# SAM_E54_Xplained_Pro_current_measurement.net
KiCad netlist of a schematic drawn in Altium Designer
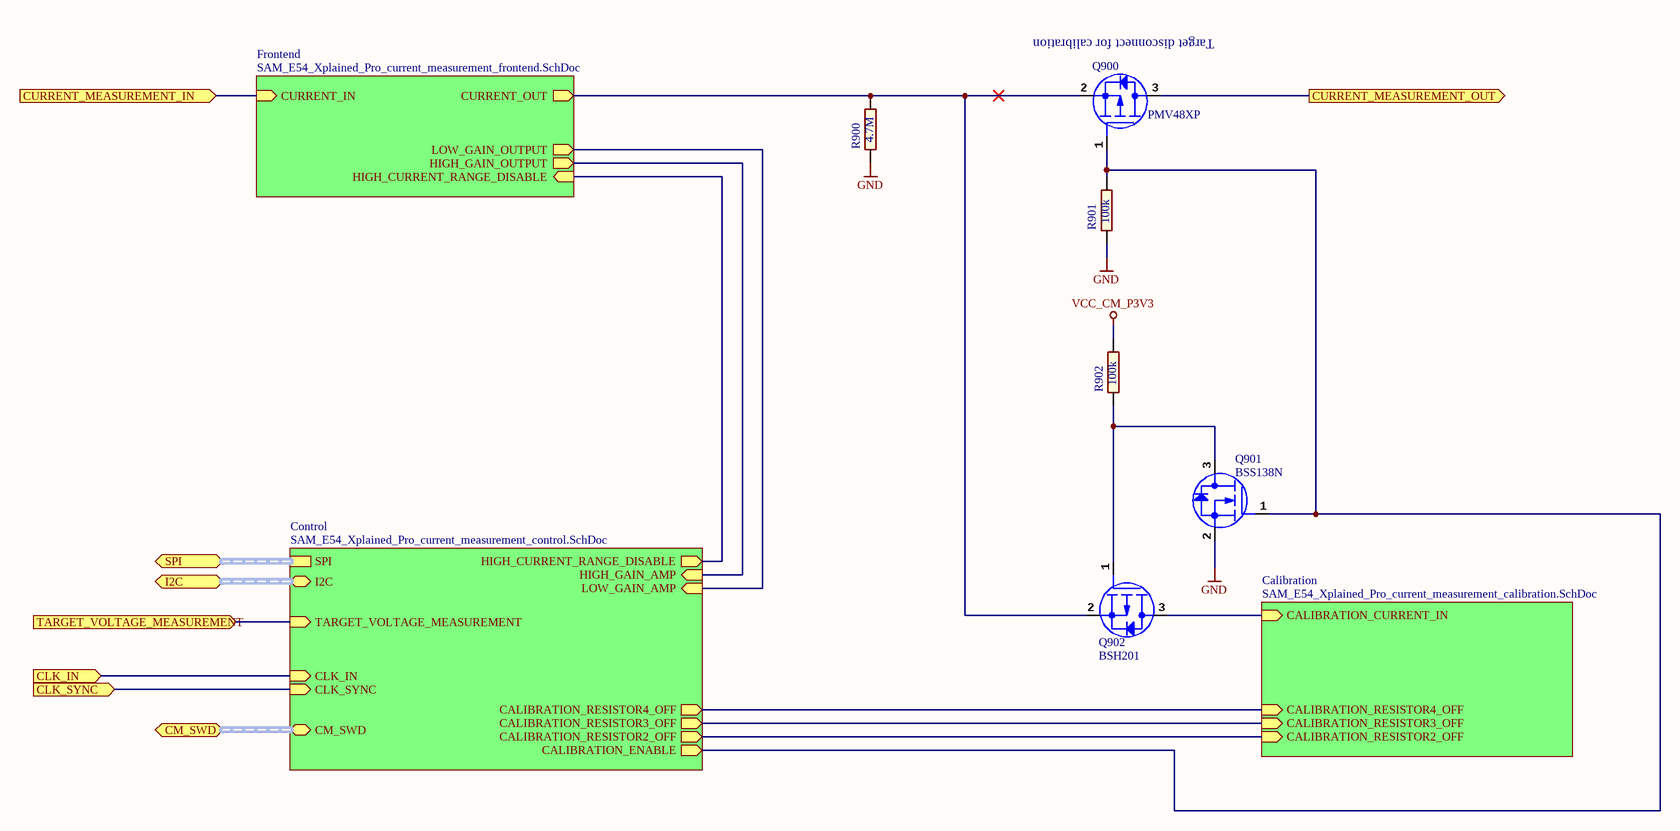
[diagram p0: SAM_E54_Xplained_Pro_current_measurement.SchDoc]

(export (version "E")
  (design (tool "Eeschema 10.0.6"))
  (components
    (comp (ref "Q900")
      (value "PMV48XP")
      (footprint "AP5-00002")
      (fields (field (name "MANUFACTURER") "NXP") (field (name "MPN") "PMV48XP,215"))
      (libsource (lib "AltiumDbLib") (part "MOSFET_P_GSD"))
    )
    (comp (ref "Q901")
      (value "BSS138N")
      (footprint "AP5-00002")
      (fields (field (name "MANUFACTURER") "Infineon"))
      (libsource (lib "AltiumDbLib") (part "MOSFET_N_GSD"))
    )
    (comp (ref "Q902")
      (value "BSH201")
      (footprint "AP5-00002")
      (fields (field (name "MANUFACTURER") "NXP") (field (name "MPN") "BSH201,215"))
      (libsource (lib "AltiumDbLib") (part "MOSFET_P_GSD"))
    )
    (comp (ref "R900")
      (value "4.7M")
      (footprint "AP2-00011")
      (description "Thick film SMD 0402 1/16W 1%")
      (fields (field (name "TOLERANCE") "1 %") (field (name "MANUFACTURER") "YAGEO CORP"))
      (libsource (lib "") (part "R2_1"))
    )
    (comp (ref "R901")
      (value "100k")
      (footprint "AP2-00011")
      (description "Thick film resistor, SMD 0402, 1/16W, 1%")
      (fields (field (name "TOLERANCE") "1 %") (field (name "MANUFACTURER") "ASJ"))
      (libsource (lib "") (part "R2_1"))
    )
    (comp (ref "R902")
      (value "100k")
      (footprint "AP2-00011")
      (description "Thick film resistor, SMD 0402, 1/16W, 1%")
      (fields (field (name "TOLERANCE") "1 %") (field (name "MANUFACTURER") "ASJ"))
      (libsource (lib "AltiumDbLib") (part "R2"))
    )
  )
  (nets
    (net (code "4") (name "/CALIBRATION_CURRENT_IN") (class "Default")
      (node (ref "Q902") (pin "3") (pinfunction "D_3") (pintype "passive"))
    )
    (net (code "5") (name "/CALIBRATION_ENABLE") (class "Default")
      (node (ref "Q900") (pin "1") (pinfunction "G_1") (pintype "passive"))
      (node (ref "Q901") (pin "1") (pinfunction "G_1") (pintype "passive"))
      (node (ref "R901") (pin "2") (pinfunction "2_2") (pintype "passive"))
    )
    (net (code "13") (name "/CURRENT_MEASUREMENT_OUT") (class "Default")
      (node (ref "Q900") (pin "3") (pinfunction "D_3") (pintype "passive"))
    )
    (net (code "14") (name "/CURRENT_OUT") (class "Default")
      (node (ref "Q900") (pin "2") (pinfunction "S_2") (pintype "passive"))
      (node (ref "Q902") (pin "2") (pinfunction "S_2") (pintype "passive"))
      (node (ref "R900") (pin "2") (pinfunction "2_2") (pintype "passive"))
    )
    (net (code "21") (name "GND") (class "Default")
      (node (ref "Q901") (pin "2") (pinfunction "S_2") (pintype "passive"))
      (node (ref "R900") (pin "1") (pinfunction "1_1") (pintype "passive"))
      (node (ref "R901") (pin "1") (pinfunction "1_1") (pintype "passive"))
    )
    (net (code "22") (name "Net-(Q901-D)") (class "Default")
      (node (ref "Q901") (pin "3") (pinfunction "D_3") (pintype "passive"))
      (node (ref "Q902") (pin "1") (pinfunction "G_1") (pintype "passive"))
      (node (ref "R902") (pin "1") (pinfunction "1_1") (pintype "passive"))
    )
    (net (code "23") (name "VCC_CM_P3V3") (class "Default")
      (node (ref "R902") (pin "2") (pinfunction "2_2") (pintype "passive"))
    )
  )
)
